# Top.net
KiCad netlist of a schematic drawn in Altium Designer
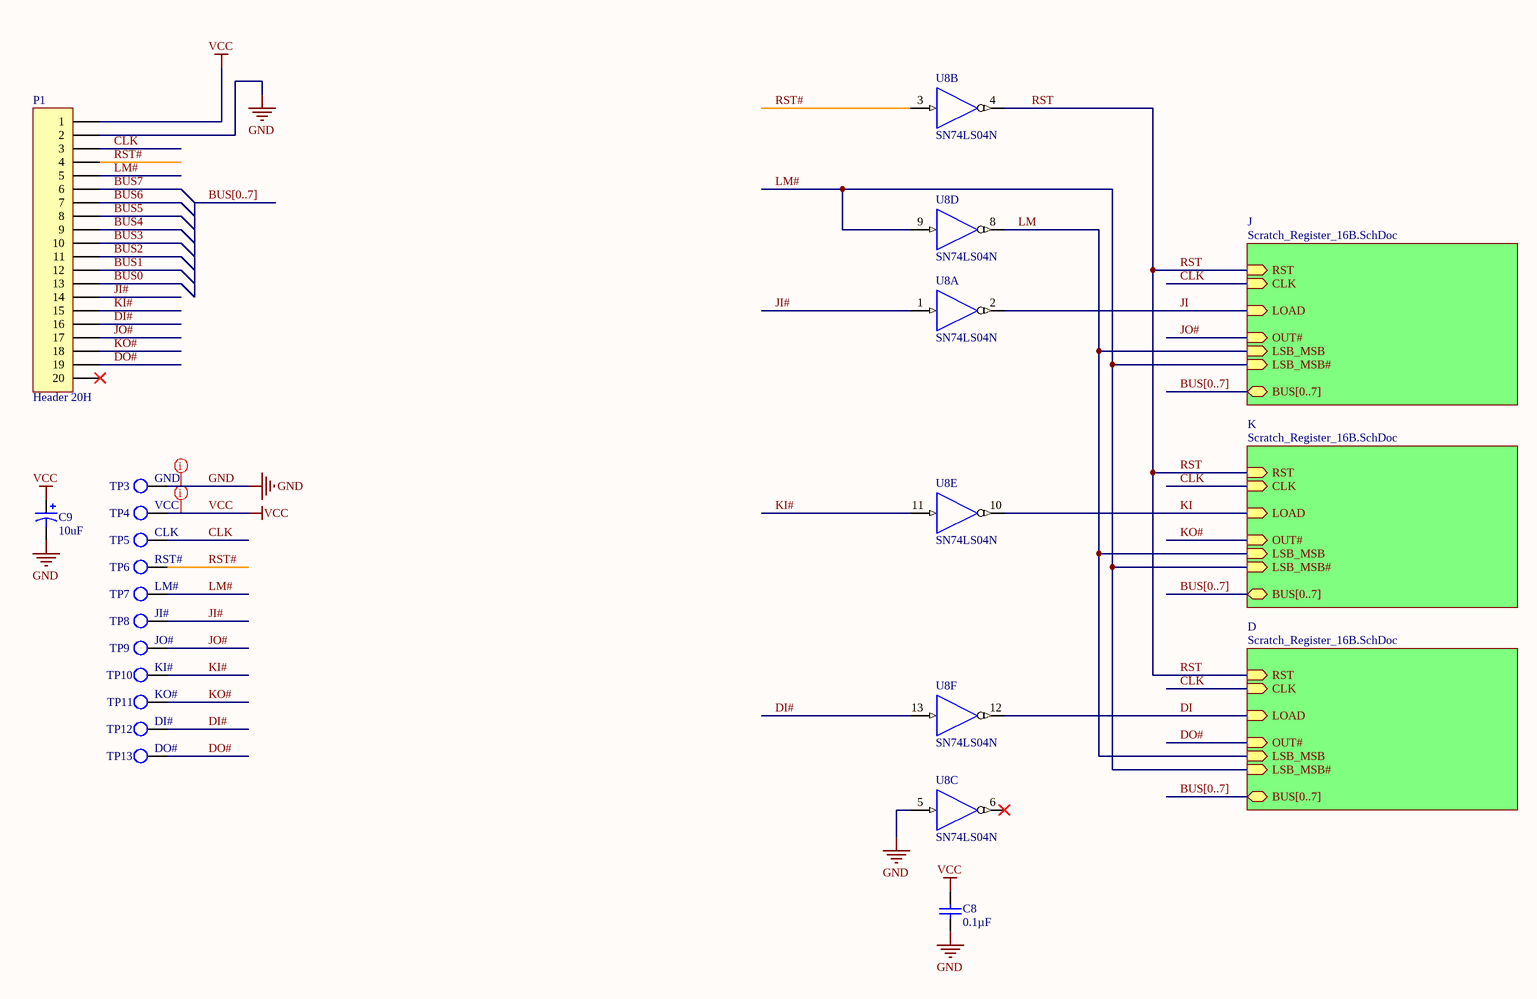
[diagram p0: Top.SchDoc]

(export (version "E")
  (design (tool "Eeschema 10.0.6"))
  (components
    (comp (ref "C8")
      (value "K104K15X7RF5TL2")
      (footprint "VISH-K104K15X7RF5TL2")
      (description "Ceramic Capacitor, 100 nF, +/- 10%, 50 V, -55 to 125 degC, 2-Pin THD, RoHS, Tape and Reel")
      (fields
        (field (name "MANUFACTURER") "Vishay")
        (field (name "TOLERANCE") "±10%")
        (field (name "CAPACITANCE") "0.1µF")
      )
      (libsource (lib "Altium Content Vault") (part "CAP-NP-2"))
    )
    (comp (ref "C9")
      (value "10uF")
      (footprint "C5x7")
      (description "Polarized Capacitor")
      (fields (field (name "Comment") "Cap Pol5") (field (name "PUBLISHER") "Altium Limited"))
      (libsource (lib "Miscellaneous Devices") (part "Cap Pol5"))
    )
    (comp (ref "P1")
      (value "Header 20H")
      (footprint "HDR1X20H")
      (description "Header, 20-Pin, Right Angle")
      (fields (field (name "PUBLISHER") "Altium Limited"))
      (libsource (lib "Miscellaneous Connectors") (part "Header 20H"))
    )
    (comp (ref "TP3") (value "GND") (footprint "KSTN-5011_V") (libsource (lib "TP") (part "TP")))
    (comp (ref "TP4") (value "VCC") (footprint "KSTN-5011_V") (libsource (lib "TP") (part "TP")))
    (comp (ref "TP5") (value "CLK") (footprint "KSTN-5011_V") (libsource (lib "TP") (part "TP")))
    (comp (ref "TP6") (value "RST#") (footprint "KSTN-5011_V") (libsource (lib "TP") (part "TP")))
    (comp (ref "TP7") (value "LM#") (footprint "KSTN-5011_V") (libsource (lib "TP") (part "TP")))
    (comp (ref "TP8") (value "JI#") (footprint "KSTN-5011_V") (libsource (lib "TP") (part "TP")))
    (comp (ref "TP9") (value "JO#") (footprint "KSTN-5011_V") (libsource (lib "TP") (part "TP")))
    (comp (ref "TP10") (value "KI#") (footprint "KSTN-5011_V") (libsource (lib "TP") (part "TP")))
    (comp (ref "TP11") (value "KO#") (footprint "KSTN-5011_V") (libsource (lib "TP") (part "TP")))
    (comp (ref "TP12") (value "DI#") (footprint "KSTN-5011_V") (libsource (lib "TP") (part "TP")))
    (comp (ref "TP13") (value "DO#") (footprint "KSTN-5011_V") (libsource (lib "TP") (part "TP")))
    (comp (ref "U8")
      (value "SN74LS04N")
      (footprint "N014")
      (description "Hex Inverter")
      (fields (field (name "PUBLISHER") "Altium Limited"))
      (libsource (lib "TI Logic Gate 2") (part "SN74LS04N"))
    )
  )
  (nets
    (net (code "1") (name "/BUS0") (class "Default")
      (node (ref "P1") (pin "13") (pinfunction "13_13") (pintype "passive"))
    )
    (net (code "2") (name "/BUS1") (class "Default")
      (node (ref "P1") (pin "12") (pinfunction "12_12") (pintype "passive"))
    )
    (net (code "3") (name "/BUS2") (class "Default")
      (node (ref "P1") (pin "11") (pinfunction "11_11") (pintype "passive"))
    )
    (net (code "4") (name "/BUS3") (class "Default")
      (node (ref "P1") (pin "10") (pinfunction "10_10") (pintype "passive"))
    )
    (net (code "5") (name "/BUS4") (class "Default")
      (node (ref "P1") (pin "9") (pinfunction "9_9") (pintype "passive"))
    )
    (net (code "6") (name "/BUS5") (class "Default")
      (node (ref "P1") (pin "8") (pinfunction "8_8") (pintype "passive"))
    )
    (net (code "7") (name "/BUS6") (class "Default")
      (node (ref "P1") (pin "7") (pinfunction "7_7") (pintype "passive"))
    )
    (net (code "8") (name "/BUS7") (class "Default")
      (node (ref "P1") (pin "6") (pinfunction "6_6") (pintype "passive"))
    )
    (net (code "10") (name "/CLK") (class "Default")
      (node (ref "P1") (pin "3") (pinfunction "3_3") (pintype "passive"))
      (node (ref "TP5") (pin "1") (pintype "passive"))
    )
    (net (code "11") (name "/DI") (class "Default")
      (node (ref "U8") (pin "12") (pinfunction "Y_12") (pintype "output"))
    )
    (net (code "12") (name "/DI#") (class "Default")
      (node (ref "P1") (pin "16") (pinfunction "16_16") (pintype "passive"))
      (node (ref "TP12") (pin "1") (pintype "passive"))
      (node (ref "U8") (pin "13") (pinfunction "A_13") (pintype "input"))
    )
    (net (code "13") (name "/DO#") (class "Default")
      (node (ref "P1") (pin "19") (pinfunction "19_19") (pintype "passive"))
      (node (ref "TP13") (pin "1") (pintype "passive"))
    )
    (net (code "14") (name "/JI") (class "Default")
      (node (ref "U8") (pin "2") (pinfunction "Y_2") (pintype "output"))
    )
    (net (code "15") (name "/JI#") (class "Default")
      (node (ref "P1") (pin "14") (pinfunction "14_14") (pintype "passive"))
      (node (ref "TP8") (pin "1") (pintype "passive"))
      (node (ref "U8") (pin "1") (pinfunction "A_1") (pintype "input"))
    )
    (net (code "16") (name "/JO#") (class "Default")
      (node (ref "P1") (pin "17") (pinfunction "17_17") (pintype "passive"))
      (node (ref "TP9") (pin "1") (pintype "passive"))
    )
    (net (code "17") (name "/KI") (class "Default")
      (node (ref "U8") (pin "10") (pinfunction "Y_10") (pintype "output"))
    )
    (net (code "18") (name "/KI#") (class "Default")
      (node (ref "P1") (pin "15") (pinfunction "15_15") (pintype "passive"))
      (node (ref "TP10") (pin "1") (pintype "passive"))
      (node (ref "U8") (pin "11") (pinfunction "A_11") (pintype "input"))
    )
    (net (code "19") (name "/KO#") (class "Default")
      (node (ref "P1") (pin "18") (pinfunction "18_18") (pintype "passive"))
      (node (ref "TP11") (pin "1") (pintype "passive"))
    )
    (net (code "20") (name "/LM") (class "Default")
      (node (ref "U8") (pin "8") (pinfunction "Y_8") (pintype "output"))
    )
    (net (code "21") (name "/LM#") (class "Default")
      (node (ref "P1") (pin "5") (pinfunction "5_5") (pintype "passive"))
      (node (ref "TP7") (pin "1") (pintype "passive"))
      (node (ref "U8") (pin "9") (pinfunction "A_9") (pintype "input"))
    )
    (net (code "22") (name "/RST") (class "Default")
      (node (ref "U8") (pin "4") (pinfunction "Y_4") (pintype "output"))
    )
    (net (code "23") (name "/RST#") (class "Default")
      (node (ref "P1") (pin "4") (pinfunction "4_4") (pintype "passive"))
      (node (ref "TP6") (pin "1") (pintype "passive"))
      (node (ref "U8") (pin "3") (pinfunction "A_3") (pintype "input"))
    )
    (net (code "24") (name "GND") (class "Default")
      (node (ref "C8") (pin "2") (pinfunction "2_2") (pintype "passive"))
      (node (ref "C9") (pin "2") (pinfunction "2_2") (pintype "passive"))
      (node (ref "P1") (pin "2") (pinfunction "2_2") (pintype "passive"))
      (node (ref "TP3") (pin "1") (pintype "passive"))
      (node (ref "U8") (pin "5") (pinfunction "A_5") (pintype "input"))
      (node (ref "U8") (pin "7") (pinfunction "GND_7") (pintype "power_in"))
    )
    (net (code "25") (name "VCC") (class "Default")
      (node (ref "C8") (pin "1") (pinfunction "1_1") (pintype "passive"))
      (node (ref "C9") (pin "1") (pinfunction "1_1") (pintype "passive"))
      (node (ref "P1") (pin "1") (pinfunction "1_1") (pintype "passive"))
      (node (ref "TP4") (pin "1") (pintype "passive"))
      (node (ref "U8") (pin "14") (pinfunction "VCC_14") (pintype "power_in"))
    )
    (net (code "26") (name "unconnected-(P1-Pad20)") (class "Default")
      (node (ref "P1") (pin "20") (pinfunction "20_20") (pintype "passive+no_connect"))
    )
    (net (code "27") (name "unconnected-(U8C-Y-Pad6)") (class "Default")
      (node (ref "U8") (pin "6") (pinfunction "Y_6") (pintype "output+no_connect"))
    )
  )
)
